# fencerSMD.net
KiCad netlist of a schematic drawn in EAGLE
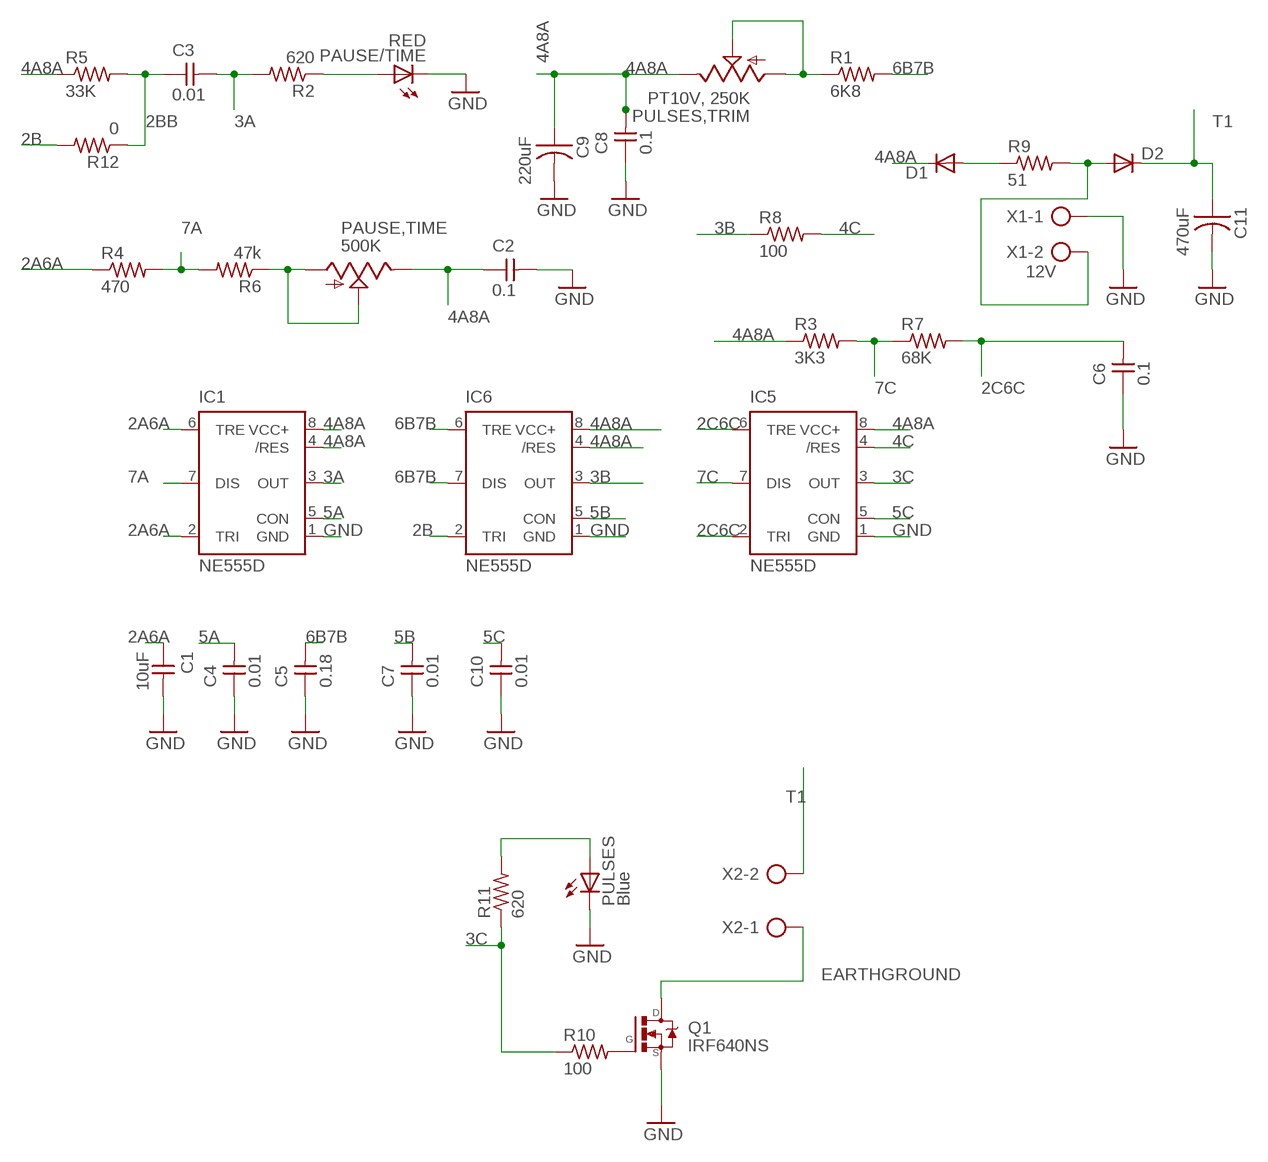
[diagram p0: schematic, sheet 1]

(export (version "E")
  (design (tool "Eeschema 10.0.6"))
  (components
    (comp (ref "C1")
      (value "10uF")
      (footprint "eagle-import:1206")
      (libsource (lib "eagle-import") (part "UNPOLARIZED_CAPACITOR1206"))
    )
    (comp (ref "C2")
      (value "0.1")
      (footprint "eagle-import:1206")
      (libsource (lib "eagle-import") (part "UNPOLARIZED_CAPACITOR1206"))
    )
    (comp (ref "C3")
      (value "0.01")
      (footprint "eagle-import:1206")
      (libsource (lib "eagle-import") (part "UNPOLARIZED_CAPACITOR1206"))
    )
    (comp (ref "C4")
      (value "0.01")
      (footprint "eagle-import:1206")
      (libsource (lib "eagle-import") (part "UNPOLARIZED_CAPACITOR1206"))
    )
    (comp (ref "C5")
      (value "0.18")
      (footprint "eagle-import:1206")
      (libsource (lib "eagle-import") (part "UNPOLARIZED_CAPACITOR1206"))
    )
    (comp (ref "C6")
      (value "0.1")
      (footprint "eagle-import:1206")
      (libsource (lib "eagle-import") (part "UNPOLARIZED_CAPACITOR1206"))
    )
    (comp (ref "C7")
      (value "0.01")
      (footprint "eagle-import:1206")
      (libsource (lib "eagle-import") (part "UNPOLARIZED_CAPACITOR1206"))
    )
    (comp (ref "C8")
      (value "0.1")
      (footprint "eagle-import:1206")
      (libsource (lib "eagle-import") (part "UNPOLARIZED_CAPACITOR1206"))
    )
    (comp (ref "C9")
      (value "220uF")
      (footprint "eagle-import:C1206")
      (libsource (lib "eagle-import") (part "CAP-US1206"))
    )
    (comp (ref "C10")
      (value "0.01")
      (footprint "eagle-import:1206")
      (libsource (lib "eagle-import") (part "UNPOLARIZED_CAPACITOR1206"))
    )
    (comp (ref "C11")
      (value "470uF")
      (footprint "eagle-import:C1206")
      (libsource (lib "eagle-import") (part "CAP-US1206"))
    )
    (comp (ref "D1")
      (value "DIODESOD123")
      (footprint "eagle-import:SOD123")
      (libsource (lib "eagle-import") (part "DIODESOD123"))
    )
    (comp (ref "D2")
      (value "DIODESOD123")
      (footprint "eagle-import:SOD123")
      (libsource (lib "eagle-import") (part "DIODESOD123"))
    )
    (comp (ref "IC1")
      (value "NE555D")
      (footprint "eagle-import:SO08")
      (libsource (lib "eagle-import") (part "NE555D"))
    )
    (comp (ref "IC5")
      (value "NE555D")
      (footprint "eagle-import:SO08")
      (libsource (lib "eagle-import") (part "NE555D"))
    )
    (comp (ref "IC6")
      (value "NE555D")
      (footprint "eagle-import:SO08")
      (libsource (lib "eagle-import") (part "NE555D"))
    )
    (comp (ref "PAUSE,TIME")
      (value "500K")
      (footprint "eagle-import:6MM")
      (libsource (lib "eagle-import") (part "TRIM"))
    )
    (comp (ref "PAUSE/TIME")
      (value "RED")
      (footprint "eagle-import:LED1206FAB")
      (libsource (lib "eagle-import") (part "LEDFAB1206"))
    )
    (comp (ref "PULSES")
      (value "Blue")
      (footprint "eagle-import:LED1206FAB")
      (libsource (lib "eagle-import") (part "LEDFAB1206"))
    )
    (comp (ref "PULSES,TRIM")
      (value "PT10V, 250K")
      (footprint "eagle-import:6MM")
      (libsource (lib "eagle-import") (part "TRIM"))
    )
    (comp (ref "Q1")
      (value "IRF640NS")
      (footprint "eagle-import:D2PAK")
      (fields (field (name "MF") "Comset Semiconductors") (field (name "MP") "IRF640"))
      (libsource (lib "eagle-import") (part "IRF640NS"))
    )
    (comp (ref "R1")
      (value "6K8")
      (footprint "eagle-import:1206")
      (libsource (lib "eagle-import") (part "RESISTOR1206"))
    )
    (comp (ref "R2")
      (value "620")
      (footprint "eagle-import:1206")
      (libsource (lib "eagle-import") (part "RESISTOR1206"))
    )
    (comp (ref "R3")
      (value "3K3")
      (footprint "eagle-import:1206")
      (libsource (lib "eagle-import") (part "RESISTOR1206"))
    )
    (comp (ref "R4")
      (value "470")
      (footprint "eagle-import:1206")
      (libsource (lib "eagle-import") (part "RESISTOR1206"))
    )
    (comp (ref "R5")
      (value "33K")
      (footprint "eagle-import:1206")
      (libsource (lib "eagle-import") (part "RESISTOR1206"))
    )
    (comp (ref "R6")
      (value "47k")
      (footprint "eagle-import:1206")
      (libsource (lib "eagle-import") (part "RESISTOR1206"))
    )
    (comp (ref "R7")
      (value "68K")
      (footprint "eagle-import:1206")
      (libsource (lib "eagle-import") (part "RESISTOR1206"))
    )
    (comp (ref "R8")
      (value "100")
      (footprint "eagle-import:1206")
      (libsource (lib "eagle-import") (part "RESISTOR1206"))
    )
    (comp (ref "R9")
      (value "51")
      (footprint "eagle-import:1206")
      (libsource (lib "eagle-import") (part "RESISTOR1206"))
    )
    (comp (ref "R10")
      (value "100")
      (footprint "eagle-import:1206")
      (libsource (lib "eagle-import") (part "RESISTOR1206"))
    )
    (comp (ref "R11")
      (value "620")
      (footprint "eagle-import:1206")
      (libsource (lib "eagle-import") (part "RESISTOR1206"))
    )
    (comp (ref "R12")
      (value "0")
      (footprint "eagle-import:1206")
      (libsource (lib "eagle-import") (part "RESISTOR1206"))
    )
    (comp (ref "X1")
      (value "12V")
      (footprint "eagle-import:AK500_2-H")
      (libsource (lib "eagle-import") (part "AK500/2-H"))
    )
    (comp (ref "X2")
      (value "AK500/2-H")
      (footprint "eagle-import:AK500_2-H")
      (libsource (lib "eagle-import") (part "AK500/2-H"))
    )
  )
  (nets
    (net (code "1") (name "/2A6A") (class "Default")
      (node (ref "C1") (pin "1") (pinfunction "1_1") (pintype "passive"))
      (node (ref "IC1") (pin "2") (pinfunction "TRI_2") (pintype "input"))
      (node (ref "IC1") (pin "6") (pinfunction "TRE_6") (pintype "input"))
      (node (ref "R4") (pin "1") (pinfunction "1_1") (pintype "passive"))
    )
    (net (code "2") (name "/2B") (class "Default")
      (node (ref "IC6") (pin "2") (pinfunction "TRI_2") (pintype "input"))
      (node (ref "R12") (pin "2") (pinfunction "2_2") (pintype "passive"))
    )
    (net (code "3") (name "/2BB") (class "Default")
      (node (ref "C3") (pin "1") (pinfunction "1_1") (pintype "passive"))
      (node (ref "R12") (pin "1") (pinfunction "1_1") (pintype "passive"))
      (node (ref "R5") (pin "2") (pinfunction "2_2") (pintype "passive"))
    )
    (net (code "4") (name "/2C6C") (class "Default")
      (node (ref "C6") (pin "2") (pinfunction "2_2") (pintype "passive"))
      (node (ref "IC5") (pin "2") (pinfunction "TRI_2") (pintype "input"))
      (node (ref "IC5") (pin "6") (pinfunction "TRE_6") (pintype "input"))
      (node (ref "R7") (pin "2") (pinfunction "2_2") (pintype "passive"))
    )
    (net (code "5") (name "/3A") (class "Default")
      (node (ref "C3") (pin "2") (pinfunction "2_2") (pintype "passive"))
      (node (ref "IC1") (pin "3") (pinfunction "OUT_3") (pintype "output"))
      (node (ref "R2") (pin "2") (pinfunction "2_2") (pintype "passive"))
    )
    (net (code "6") (name "/3B") (class "Default")
      (node (ref "IC6") (pin "3") (pinfunction "OUT_3") (pintype "output"))
      (node (ref "R8") (pin "1") (pinfunction "1_1") (pintype "passive"))
    )
    (net (code "7") (name "/3C") (class "Default")
      (node (ref "IC5") (pin "3") (pinfunction "OUT_3") (pintype "output"))
      (node (ref "R10") (pin "1") (pinfunction "1_1") (pintype "passive"))
      (node (ref "R11") (pin "1") (pinfunction "1_1") (pintype "passive"))
    )
    (net (code "8") (name "/4A8A") (class "Default")
      (node (ref "C2") (pin "1") (pinfunction "1_1") (pintype "passive"))
      (node (ref "C8") (pin "2") (pinfunction "2_2") (pintype "passive"))
      (node (ref "C9") (pin "1") (pinfunction "1_1") (pintype "passive"))
      (node (ref "D1") (pin "CATHODE") (pinfunction "C_CATHODE") (pintype "passive"))
      (node (ref "IC1") (pin "4") (pinfunction "/RES_4") (pintype "input"))
      (node (ref "IC1") (pin "8") (pinfunction "VCC+_8") (pintype "power_in"))
      (node (ref "IC5") (pin "8") (pinfunction "VCC+_8") (pintype "power_in"))
      (node (ref "IC6") (pin "4") (pinfunction "/RES_4") (pintype "input"))
      (node (ref "IC6") (pin "8") (pinfunction "VCC+_8") (pintype "power_in"))
      (node (ref "PAUSE,TIME") (pin "E") (pinfunction "E_E") (pintype "passive"))
      (node (ref "PULSES,TRIM") (pin "E") (pinfunction "E_E") (pintype "passive"))
      (node (ref "R3") (pin "1") (pinfunction "1_1") (pintype "passive"))
      (node (ref "R5") (pin "1") (pinfunction "1_1") (pintype "passive"))
    )
    (net (code "9") (name "/4C") (class "Default")
      (node (ref "IC5") (pin "4") (pinfunction "/RES_4") (pintype "input"))
      (node (ref "R8") (pin "2") (pinfunction "2_2") (pintype "passive"))
    )
    (net (code "10") (name "/5A") (class "Default")
      (node (ref "C4") (pin "2") (pinfunction "2_2") (pintype "passive"))
      (node (ref "IC1") (pin "5") (pinfunction "CON_5") (pintype "input"))
    )
    (net (code "11") (name "/5B") (class "Default")
      (node (ref "C7") (pin "2") (pinfunction "2_2") (pintype "passive"))
      (node (ref "IC6") (pin "5") (pinfunction "CON_5") (pintype "input"))
    )
    (net (code "12") (name "/5C") (class "Default")
      (node (ref "C10") (pin "2") (pinfunction "2_2") (pintype "passive"))
      (node (ref "IC5") (pin "5") (pinfunction "CON_5") (pintype "input"))
    )
    (net (code "13") (name "/6B7B") (class "Default")
      (node (ref "C5") (pin "2") (pinfunction "2_2") (pintype "passive"))
      (node (ref "IC6") (pin "6") (pinfunction "TRE_6") (pintype "input"))
      (node (ref "IC6") (pin "7") (pinfunction "DIS_7") (pintype "input"))
      (node (ref "R1") (pin "2") (pinfunction "2_2") (pintype "passive"))
    )
    (net (code "14") (name "/7A") (class "Default")
      (node (ref "IC1") (pin "7") (pinfunction "DIS_7") (pintype "input"))
      (node (ref "R4") (pin "2") (pinfunction "2_2") (pintype "passive"))
      (node (ref "R6") (pin "2") (pinfunction "2_2") (pintype "passive"))
    )
    (net (code "15") (name "/7C") (class "Default")
      (node (ref "IC5") (pin "7") (pinfunction "DIS_7") (pintype "input"))
      (node (ref "R3") (pin "2") (pinfunction "2_2") (pintype "passive"))
      (node (ref "R7") (pin "1") (pinfunction "1_1") (pintype "passive"))
    )
    (net (code "16") (name "/EARTHGROUND") (class "Default")
      (node (ref "Q1") (pin "2") (pinfunction "D_2") (pintype "passive"))
      (node (ref "X2") (pin "1") (pinfunction "KL_1") (pintype "passive"))
    )
    (net (code "17") (name "/T1") (class "Default")
      (node (ref "C11") (pin "1") (pinfunction "1_1") (pintype "passive"))
      (node (ref "D2") (pin "CATHODE") (pinfunction "C_CATHODE") (pintype "passive"))
      (node (ref "X2") (pin "2") (pinfunction "KL_2") (pintype "passive"))
    )
    (net (code "18") (name "GND") (class "Default")
      (node (ref "C1") (pin "2") (pinfunction "2_2") (pintype "passive"))
      (node (ref "C10") (pin "1") (pinfunction "1_1") (pintype "passive"))
      (node (ref "C11") (pin "2") (pinfunction "2_2") (pintype "passive"))
      (node (ref "C2") (pin "2") (pinfunction "2_2") (pintype "passive"))
      (node (ref "C4") (pin "1") (pinfunction "1_1") (pintype "passive"))
      (node (ref "C5") (pin "1") (pinfunction "1_1") (pintype "passive"))
      (node (ref "C6") (pin "1") (pinfunction "1_1") (pintype "passive"))
      (node (ref "C7") (pin "1") (pinfunction "1_1") (pintype "passive"))
      (node (ref "C8") (pin "1") (pinfunction "1_1") (pintype "passive"))
      (node (ref "C9") (pin "2") (pinfunction "2_2") (pintype "passive"))
      (node (ref "IC1") (pin "1") (pinfunction "GND_1") (pintype "power_in"))
      (node (ref "IC5") (pin "1") (pinfunction "GND_1") (pintype "power_in"))
      (node (ref "IC6") (pin "1") (pinfunction "GND_1") (pintype "power_in"))
      (node (ref "PAUSE/TIME") (pin "2") (pinfunction "C_2") (pintype "passive"))
      (node (ref "PULSES") (pin "2") (pinfunction "C_2") (pintype "passive"))
      (node (ref "Q1") (pin "3") (pinfunction "S_3") (pintype "passive"))
      (node (ref "X1") (pin "1") (pinfunction "KL_1") (pintype "passive"))
    )
    (net (code "19") (name "Net-(D1-A)") (class "Default")
      (node (ref "D1") (pin "ANODE") (pinfunction "A_ANODE") (pintype "passive"))
      (node (ref "R9") (pin "1") (pinfunction "1_1") (pintype "passive"))
    )
    (net (code "20") (name "Net-(D2-A)") (class "Default")
      (node (ref "D2") (pin "ANODE") (pinfunction "A_ANODE") (pintype "passive"))
      (node (ref "R9") (pin "2") (pinfunction "2_2") (pintype "passive"))
      (node (ref "X1") (pin "2") (pinfunction "KL_2") (pintype "passive"))
    )
    (net (code "21") (name "Net-(PAUSE,TIME-PadA)") (class "Default")
      (node (ref "PAUSE,TIME") (pin "A") (pinfunction "A_A") (pintype "passive"))
      (node (ref "PAUSE,TIME") (pin "S") (pinfunction "S_S") (pintype "passive"))
      (node (ref "R6") (pin "1") (pinfunction "1_1") (pintype "passive"))
    )
    (net (code "22") (name "Net-(PAUSE/TIME-A)") (class "Default")
      (node (ref "PAUSE/TIME") (pin "1") (pinfunction "A_1") (pintype "passive"))
      (node (ref "R2") (pin "1") (pinfunction "1_1") (pintype "passive"))
    )
    (net (code "23") (name "Net-(PULSES,TRIM-PadA)") (class "Default")
      (node (ref "PULSES,TRIM") (pin "A") (pinfunction "A_A") (pintype "passive"))
      (node (ref "PULSES,TRIM") (pin "S") (pinfunction "S_S") (pintype "passive"))
      (node (ref "R1") (pin "1") (pinfunction "1_1") (pintype "passive"))
    )
    (net (code "24") (name "Net-(PULSES-A)") (class "Default")
      (node (ref "PULSES") (pin "1") (pinfunction "A_1") (pintype "passive"))
      (node (ref "R11") (pin "2") (pinfunction "2_2") (pintype "passive"))
    )
    (net (code "25") (name "Net-(Q1-G)") (class "Default")
      (node (ref "Q1") (pin "1") (pinfunction "G_1") (pintype "passive"))
      (node (ref "R10") (pin "2") (pinfunction "2_2") (pintype "passive"))
    )
  )
)
